# RAM.net
KiCad netlist of a schematic drawn in Altium Designer
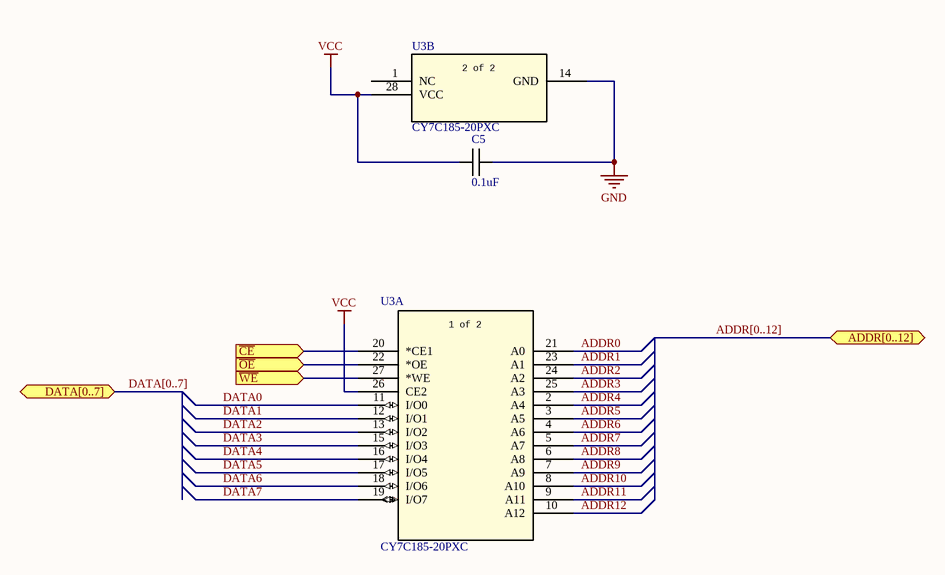
[diagram p0: RAM.SchDoc]

(export (version "E")
  (design (tool "Eeschema 10.0.6"))
  (components
    (comp (ref "C5") (value "0.1uF") (footprint "SMD 0603") (libsource (lib "Maks_lib") (part "Capasitor")))
    (comp (ref "U3")
      (value "CY7C185-20PXC")
      (footprint "DIP-28")
      (description "IC SRAM 64KBIT 20NS 28DIP")
      (libsource (lib "Maks_lib") (part "CY7C185-20PXC"))
    )
  )
  (nets
    (net (code "1") (name "/ADDR0") (class "Default")
      (node (ref "U3") (pin "21") (pinfunction "A0_21") (pintype "passive"))
    )
    (net (code "2") (name "/ADDR1") (class "Default")
      (node (ref "U3") (pin "23") (pinfunction "A1_23") (pintype "passive"))
    )
    (net (code "3") (name "/ADDR2") (class "Default")
      (node (ref "U3") (pin "24") (pinfunction "A2_24") (pintype "passive"))
    )
    (net (code "4") (name "/ADDR3") (class "Default")
      (node (ref "U3") (pin "25") (pinfunction "A3_25") (pintype "passive"))
    )
    (net (code "5") (name "/ADDR4") (class "Default")
      (node (ref "U3") (pin "2") (pinfunction "A4_2") (pintype "passive"))
    )
    (net (code "6") (name "/ADDR5") (class "Default")
      (node (ref "U3") (pin "3") (pinfunction "A5_3") (pintype "passive"))
    )
    (net (code "7") (name "/ADDR6") (class "Default")
      (node (ref "U3") (pin "4") (pinfunction "A6_4") (pintype "passive"))
    )
    (net (code "8") (name "/ADDR7") (class "Default")
      (node (ref "U3") (pin "5") (pinfunction "A7_5") (pintype "passive"))
    )
    (net (code "9") (name "/ADDR8") (class "Default")
      (node (ref "U3") (pin "6") (pinfunction "A8_6") (pintype "passive"))
    )
    (net (code "10") (name "/ADDR9") (class "Default")
      (node (ref "U3") (pin "7") (pinfunction "A9_7") (pintype "passive"))
    )
    (net (code "11") (name "/ADDR10") (class "Default")
      (node (ref "U3") (pin "8") (pinfunction "A10_8") (pintype "passive"))
    )
    (net (code "12") (name "/ADDR11") (class "Default")
      (node (ref "U3") (pin "9") (pinfunction "A11_9") (pintype "passive"))
    )
    (net (code "13") (name "/ADDR12") (class "Default")
      (node (ref "U3") (pin "10") (pinfunction "A12_10") (pintype "passive"))
    )
    (net (code "15") (name "/CE") (class "Default")
      (node (ref "U3") (pin "20") (pinfunction "*CE1_20") (pintype "passive"))
    )
    (net (code "16") (name "/DATA0") (class "Default")
      (node (ref "U3") (pin "11") (pinfunction "I/O0_11") (pintype "bidirectional"))
    )
    (net (code "17") (name "/DATA1") (class "Default")
      (node (ref "U3") (pin "12") (pinfunction "I/O1_12") (pintype "bidirectional"))
    )
    (net (code "18") (name "/DATA2") (class "Default")
      (node (ref "U3") (pin "13") (pinfunction "I/O2_13") (pintype "bidirectional"))
    )
    (net (code "19") (name "/DATA3") (class "Default")
      (node (ref "U3") (pin "15") (pinfunction "I/O3_15") (pintype "bidirectional"))
    )
    (net (code "20") (name "/DATA4") (class "Default")
      (node (ref "U3") (pin "16") (pinfunction "I/O4_16") (pintype "bidirectional"))
    )
    (net (code "21") (name "/DATA5") (class "Default")
      (node (ref "U3") (pin "17") (pinfunction "I/O5_17") (pintype "bidirectional"))
    )
    (net (code "22") (name "/DATA6") (class "Default")
      (node (ref "U3") (pin "18") (pinfunction "I/O6_18") (pintype "bidirectional"))
    )
    (net (code "23") (name "/DATA7") (class "Default")
      (node (ref "U3") (pin "19") (pinfunction "I/O7_19") (pintype "bidirectional"))
    )
    (net (code "25") (name "/OE") (class "Default")
      (node (ref "U3") (pin "22") (pinfunction "*OE_22") (pintype "passive"))
    )
    (net (code "26") (name "/WE") (class "Default")
      (node (ref "U3") (pin "27") (pinfunction "*WE_27") (pintype "passive"))
    )
    (net (code "27") (name "GND") (class "Default")
      (node (ref "C5") (pin "2") (pinfunction "2_2") (pintype "passive"))
      (node (ref "U3") (pin "14") (pinfunction "GND_14") (pintype "power_in"))
    )
    (net (code "28") (name "VCC") (class "Default")
      (node (ref "C5") (pin "1") (pinfunction "1_1") (pintype "passive"))
      (node (ref "U3") (pin "26") (pinfunction "CE2_26") (pintype "passive"))
      (node (ref "U3") (pin "28") (pinfunction "VCC_28") (pintype "power_in"))
    )
    (net (code "29") (name "unconnected-(U3B-NC-Pad1)") (class "Default")
      (node (ref "U3") (pin "1") (pinfunction "NC_1") (pintype "passive"))
    )
  )
)
